# GeigerMuller_shield.net
KiCad netlist of a schematic drawn in EAGLE
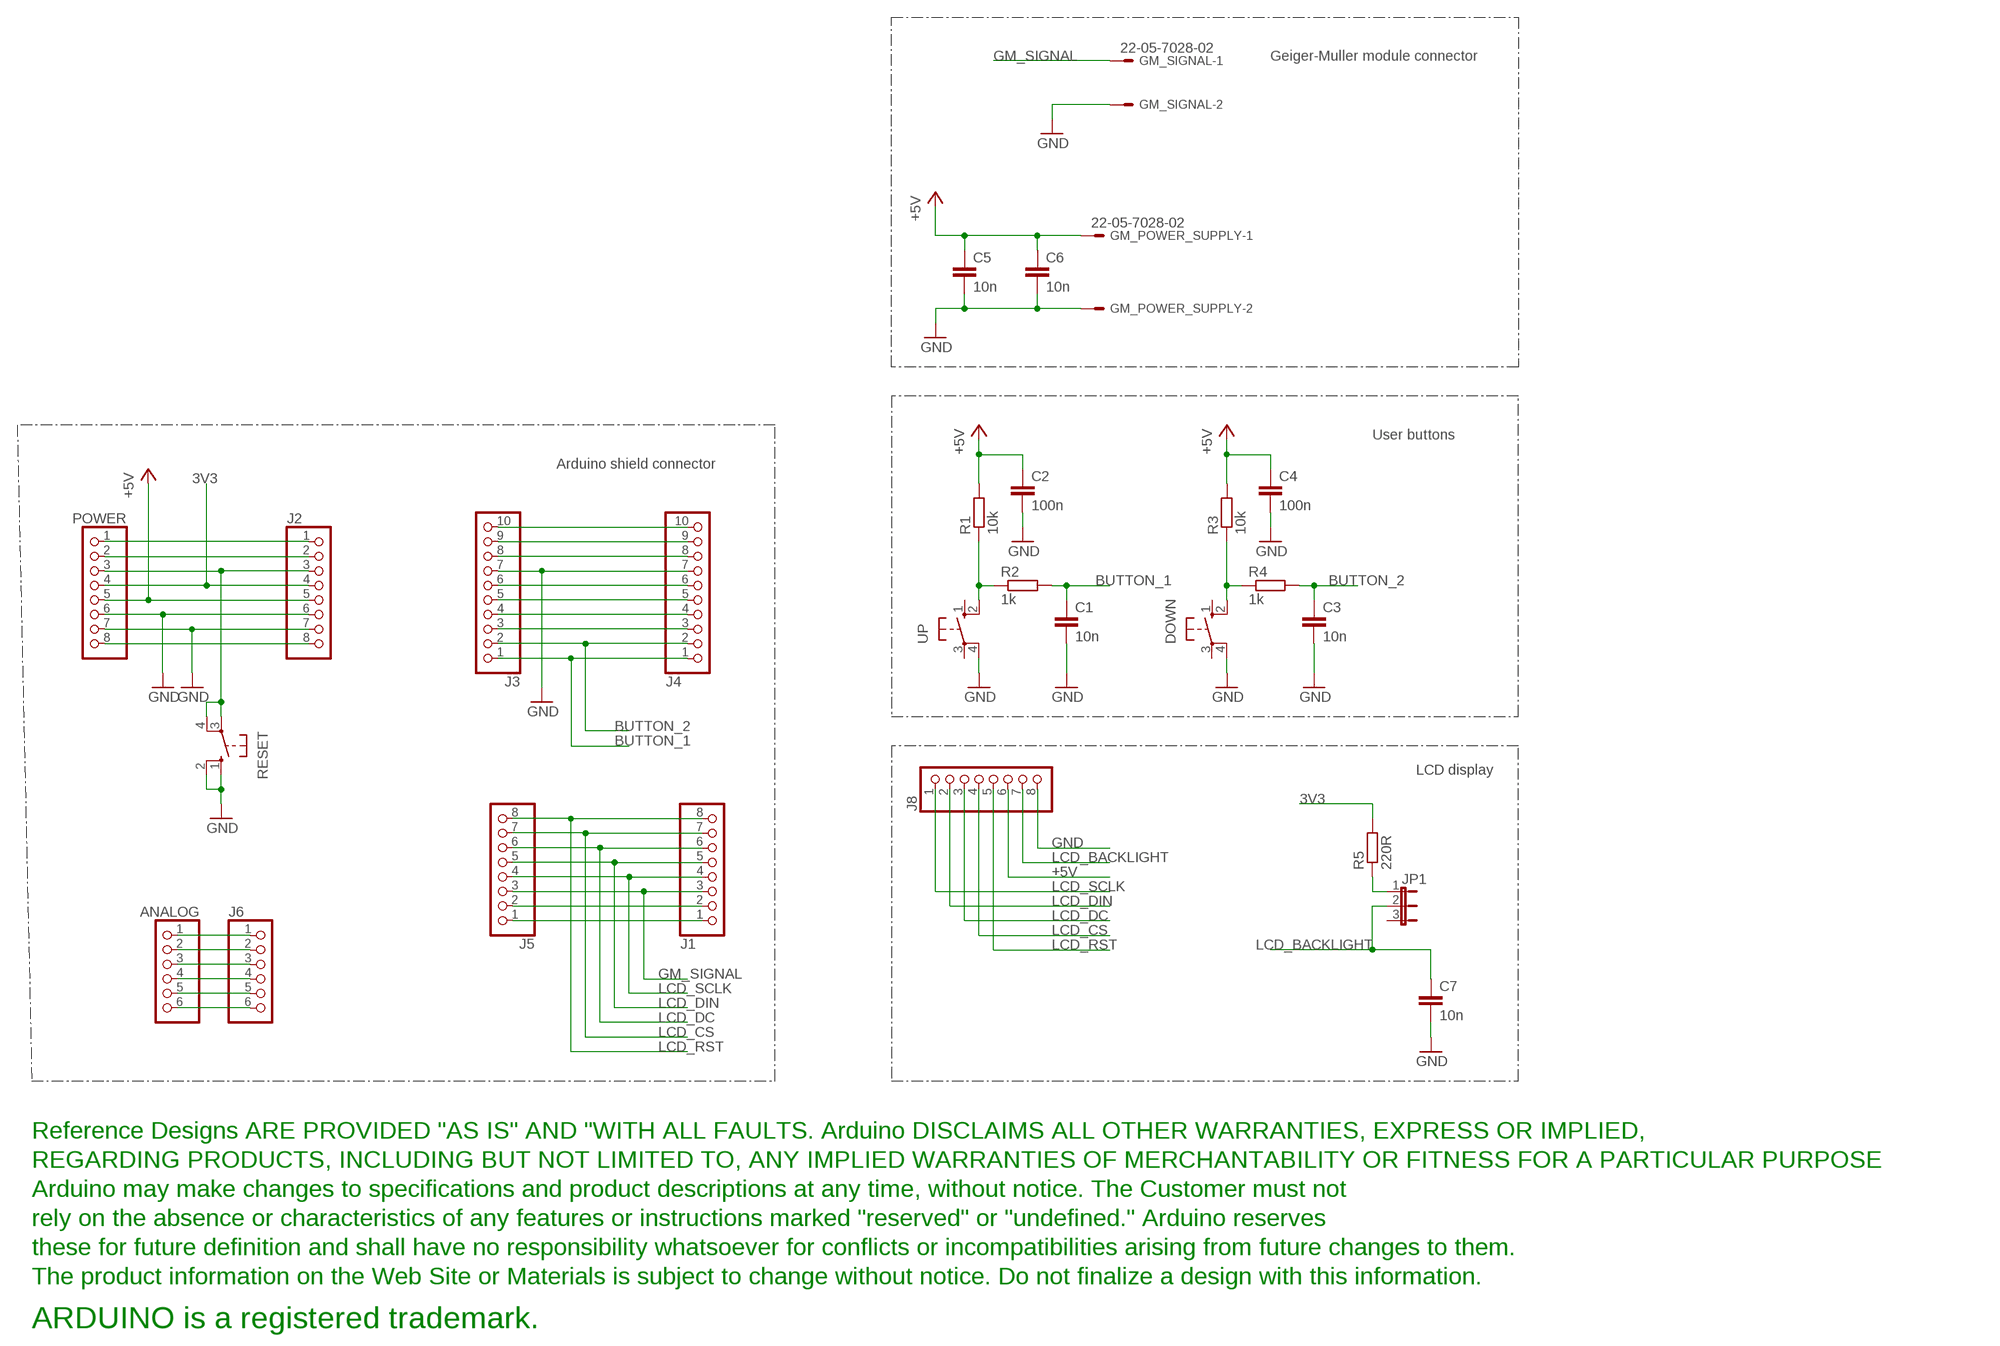
[diagram p0: schematic, sheet 1]

(export (version "E")
  (design (tool "Eeschema 10.0.6"))
  (components
    (comp (ref "ANALOG")
      (value "PINHD-1X6")
      (footprint "eagle-import:1X06")
      (libsource (lib "eagle-import") (part "PINHD-1X6"))
    )
    (comp (ref "C1")
      (value "10n")
      (footprint "eagle-import:C0805K")
      (libsource (lib "eagle-import") (part "C-EUC0805K"))
    )
    (comp (ref "C2")
      (value "100n")
      (footprint "eagle-import:C0805K")
      (libsource (lib "eagle-import") (part "C-EUC0805K"))
    )
    (comp (ref "C3")
      (value "10n")
      (footprint "eagle-import:C0805K")
      (libsource (lib "eagle-import") (part "C-EUC0805K"))
    )
    (comp (ref "C4")
      (value "100n")
      (footprint "eagle-import:C0805K")
      (libsource (lib "eagle-import") (part "C-EUC0805K"))
    )
    (comp (ref "C5")
      (value "10n")
      (footprint "eagle-import:C0805K")
      (libsource (lib "eagle-import") (part "C-EUC0805K"))
    )
    (comp (ref "C6")
      (value "10n")
      (footprint "eagle-import:C0805K")
      (libsource (lib "eagle-import") (part "C-EUC0805K"))
    )
    (comp (ref "C7")
      (value "10n")
      (footprint "eagle-import:C0805K")
      (libsource (lib "eagle-import") (part "C-EUC0805K"))
    )
    (comp (ref "DOWN")
      (value "10-XX")
      (footprint "eagle-import:B3F-10XX")
      (fields (field (name "MPN") "B3F-1000"))
      (libsource (lib "eagle-import") (part "10-XX"))
    )
    (comp (ref "GM_POWER_SUPPLY")
      (value "22-05-7028-02")
      (footprint "eagle-import:7395-02")
      (libsource (lib "eagle-import") (part "22-?-0205-7028"))
    )
    (comp (ref "GM_SIGNAL")
      (value "22-05-7028-02")
      (footprint "eagle-import:7395-02")
      (libsource (lib "eagle-import") (part "22-?-0205-7028"))
    )
    (comp (ref "J1")
      (value "PINHD-1X8TH")
      (footprint "eagle-import:1X08-TH")
      (libsource (lib "eagle-import") (part "PINHD-1X8TH"))
    )
    (comp (ref "J2")
      (value "PINHD-1X8TH")
      (footprint "eagle-import:1X08-TH")
      (libsource (lib "eagle-import") (part "PINHD-1X8TH"))
    )
    (comp (ref "J3")
      (value "PINHD-1X10TH")
      (footprint "eagle-import:1X10-TH")
      (libsource (lib "eagle-import") (part "PINHD-1X10TH"))
    )
    (comp (ref "J4")
      (value "PINHD-1X10TH")
      (footprint "eagle-import:1X10-TH")
      (libsource (lib "eagle-import") (part "PINHD-1X10TH"))
    )
    (comp (ref "J5")
      (value "PINHD-1X8TH")
      (footprint "eagle-import:1X08-TH")
      (libsource (lib "eagle-import") (part "PINHD-1X8TH"))
    )
    (comp (ref "J6")
      (value "PINHD-1X6")
      (footprint "eagle-import:1X06")
      (libsource (lib "eagle-import") (part "PINHD-1X6"))
    )
    (comp (ref "J8")
      (value "PINHD-1X8TH")
      (footprint "eagle-import:1X08-TH")
      (libsource (lib "eagle-import") (part "PINHD-1X8TH"))
    )
    (comp (ref "JP1")
      (value "JP2E")
      (footprint "eagle-import:JP2")
      (libsource (lib "eagle-import") (part "JP2E"))
    )
    (comp (ref "POWER")
      (value "PINHD-1X8TH")
      (footprint "eagle-import:1X08-TH")
      (libsource (lib "eagle-import") (part "PINHD-1X8TH"))
    )
    (comp (ref "R1")
      (value "10k")
      (footprint "eagle-import:R0805")
      (libsource (lib "eagle-import") (part "R-EU_R0805"))
    )
    (comp (ref "R2")
      (value "1k")
      (footprint "eagle-import:R0805")
      (libsource (lib "eagle-import") (part "R-EU_R0805"))
    )
    (comp (ref "R3")
      (value "10k")
      (footprint "eagle-import:R0805")
      (libsource (lib "eagle-import") (part "R-EU_R0805"))
    )
    (comp (ref "R4")
      (value "1k")
      (footprint "eagle-import:R0805")
      (libsource (lib "eagle-import") (part "R-EU_R0805"))
    )
    (comp (ref "R5")
      (value "220R")
      (footprint "eagle-import:0207_10")
      (libsource (lib "eagle-import") (part "R-EU_0207/10"))
    )
    (comp (ref "RESET")
      (value "10-XX")
      (footprint "eagle-import:B3F-10XX")
      (fields (field (name "MPN") "B3F-1000"))
      (libsource (lib "eagle-import") (part "10-XX"))
    )
    (comp (ref "U$1")
      (value "DISCLAIMER")
      (footprint "eagle-import:DISCLAIMER")
      (libsource (lib "eagle-import") (part "DISCLAIMER"))
    )
    (comp (ref "UP")
      (value "10-XX")
      (footprint "eagle-import:B3F-10XX")
      (fields (field (name "MPN") "B3F-1000"))
      (libsource (lib "eagle-import") (part "10-XX"))
    )
  )
  (nets
    (net (code "1") (name "+5V") (class "Default")
      (node (ref "C2") (pin "1") (pinfunction "1_1") (pintype "passive"))
      (node (ref "C4") (pin "1") (pinfunction "1_1") (pintype "passive"))
      (node (ref "C5") (pin "1") (pinfunction "1_1") (pintype "passive"))
      (node (ref "C6") (pin "1") (pinfunction "1_1") (pintype "passive"))
      (node (ref "GM_POWER_SUPPLY") (pin "1") (pinfunction "S_1") (pintype "passive"))
      (node (ref "J2") (pin "5") (pinfunction "5_5") (pintype "passive"))
      (node (ref "J8") (pin "6") (pinfunction "6_6") (pintype "passive"))
      (node (ref "POWER") (pin "5") (pinfunction "5_5") (pintype "passive"))
      (node (ref "R1") (pin "2") (pinfunction "2_2") (pintype "passive"))
      (node (ref "R3") (pin "2") (pinfunction "2_2") (pintype "passive"))
    )
    (net (code "2") (name "/3V3") (class "Default")
      (node (ref "J2") (pin "4") (pinfunction "4_4") (pintype "passive"))
      (node (ref "POWER") (pin "4") (pinfunction "4_4") (pintype "passive"))
      (node (ref "R5") (pin "2") (pinfunction "2_2") (pintype "passive"))
    )
    (net (code "3") (name "/BUTTON_1") (class "Default")
      (node (ref "C1") (pin "1") (pinfunction "1_1") (pintype "passive"))
      (node (ref "J3") (pin "1") (pinfunction "1_1") (pintype "passive"))
      (node (ref "J4") (pin "1") (pinfunction "1_1") (pintype "passive"))
      (node (ref "R2") (pin "2") (pinfunction "2_2") (pintype "passive"))
    )
    (net (code "4") (name "/BUTTON_2") (class "Default")
      (node (ref "C3") (pin "1") (pinfunction "1_1") (pintype "passive"))
      (node (ref "J3") (pin "2") (pinfunction "2_2") (pintype "passive"))
      (node (ref "J4") (pin "2") (pinfunction "2_2") (pintype "passive"))
      (node (ref "R4") (pin "2") (pinfunction "2_2") (pintype "passive"))
    )
    (net (code "5") (name "/GM_SIGNAL") (class "Default")
      (node (ref "GM_SIGNAL") (pin "1") (pinfunction "S_1") (pintype "passive"))
      (node (ref "J1") (pin "3") (pinfunction "3_3") (pintype "passive"))
      (node (ref "J5") (pin "3") (pinfunction "3_3") (pintype "passive"))
    )
    (net (code "6") (name "/LCD_BACKLIGHT") (class "Default")
      (node (ref "C7") (pin "1") (pinfunction "1_1") (pintype "passive"))
      (node (ref "J8") (pin "7") (pinfunction "7_7") (pintype "passive"))
      (node (ref "JP1") (pin "2") (pinfunction "2_2") (pintype "passive"))
    )
    (net (code "7") (name "/LCD_CS") (class "Default")
      (node (ref "J1") (pin "7") (pinfunction "7_7") (pintype "passive"))
      (node (ref "J5") (pin "7") (pinfunction "7_7") (pintype "passive"))
      (node (ref "J8") (pin "4") (pinfunction "4_4") (pintype "passive"))
    )
    (net (code "8") (name "/LCD_DC") (class "Default")
      (node (ref "J1") (pin "6") (pinfunction "6_6") (pintype "passive"))
      (node (ref "J5") (pin "6") (pinfunction "6_6") (pintype "passive"))
      (node (ref "J8") (pin "3") (pinfunction "3_3") (pintype "passive"))
    )
    (net (code "9") (name "/LCD_DIN") (class "Default")
      (node (ref "J1") (pin "5") (pinfunction "5_5") (pintype "passive"))
      (node (ref "J5") (pin "5") (pinfunction "5_5") (pintype "passive"))
      (node (ref "J8") (pin "2") (pinfunction "2_2") (pintype "passive"))
    )
    (net (code "10") (name "/LCD_RST") (class "Default")
      (node (ref "J1") (pin "8") (pinfunction "8_8") (pintype "passive"))
      (node (ref "J5") (pin "8") (pinfunction "8_8") (pintype "passive"))
      (node (ref "J8") (pin "5") (pinfunction "5_5") (pintype "passive"))
    )
    (net (code "11") (name "/LCD_SCLK") (class "Default")
      (node (ref "J1") (pin "4") (pinfunction "4_4") (pintype "passive"))
      (node (ref "J5") (pin "4") (pinfunction "4_4") (pintype "passive"))
      (node (ref "J8") (pin "1") (pinfunction "1_1") (pintype "passive"))
    )
    (net (code "12") (name "GND") (class "Default")
      (node (ref "C1") (pin "2") (pinfunction "2_2") (pintype "passive"))
      (node (ref "C2") (pin "2") (pinfunction "2_2") (pintype "passive"))
      (node (ref "C3") (pin "2") (pinfunction "2_2") (pintype "passive"))
      (node (ref "C4") (pin "2") (pinfunction "2_2") (pintype "passive"))
      (node (ref "C5") (pin "2") (pinfunction "2_2") (pintype "passive"))
      (node (ref "C6") (pin "2") (pinfunction "2_2") (pintype "passive"))
      (node (ref "C7") (pin "2") (pinfunction "2_2") (pintype "passive"))
      (node (ref "DOWN") (pin "4") (pinfunction "P1_4") (pintype "passive"))
      (node (ref "GM_POWER_SUPPLY") (pin "2") (pinfunction "S_2") (pintype "passive"))
      (node (ref "GM_SIGNAL") (pin "2") (pinfunction "S_2") (pintype "passive"))
      (node (ref "J2") (pin "6") (pinfunction "6_6") (pintype "passive"))
      (node (ref "J2") (pin "7") (pinfunction "7_7") (pintype "passive"))
      (node (ref "J3") (pin "7") (pinfunction "7_7") (pintype "passive"))
      (node (ref "J4") (pin "7") (pinfunction "7_7") (pintype "passive"))
      (node (ref "J8") (pin "8") (pinfunction "8_8") (pintype "passive"))
      (node (ref "POWER") (pin "6") (pinfunction "6_6") (pintype "passive"))
      (node (ref "POWER") (pin "7") (pinfunction "7_7") (pintype "passive"))
      (node (ref "RESET") (pin "1") (pinfunction "S_1") (pintype "passive"))
      (node (ref "RESET") (pin "2") (pinfunction "S1_2") (pintype "passive"))
      (node (ref "UP") (pin "4") (pinfunction "P1_4") (pintype "passive"))
    )
    (net (code "13") (name "Net-(ANALOG-Pad1)") (class "Default")
      (node (ref "ANALOG") (pin "1") (pinfunction "1_1") (pintype "passive"))
      (node (ref "J6") (pin "1") (pinfunction "1_1") (pintype "passive"))
    )
    (net (code "14") (name "Net-(ANALOG-Pad2)") (class "Default")
      (node (ref "ANALOG") (pin "2") (pinfunction "2_2") (pintype "passive"))
      (node (ref "J6") (pin "2") (pinfunction "2_2") (pintype "passive"))
    )
    (net (code "15") (name "Net-(ANALOG-Pad3)") (class "Default")
      (node (ref "ANALOG") (pin "3") (pinfunction "3_3") (pintype "passive"))
      (node (ref "J6") (pin "3") (pinfunction "3_3") (pintype "passive"))
    )
    (net (code "16") (name "Net-(ANALOG-Pad4)") (class "Default")
      (node (ref "ANALOG") (pin "4") (pinfunction "4_4") (pintype "passive"))
      (node (ref "J6") (pin "4") (pinfunction "4_4") (pintype "passive"))
    )
    (net (code "17") (name "Net-(ANALOG-Pad5)") (class "Default")
      (node (ref "ANALOG") (pin "5") (pinfunction "5_5") (pintype "passive"))
      (node (ref "J6") (pin "5") (pinfunction "5_5") (pintype "passive"))
    )
    (net (code "18") (name "Net-(ANALOG-Pad6)") (class "Default")
      (node (ref "ANALOG") (pin "6") (pinfunction "6_6") (pintype "passive"))
      (node (ref "J6") (pin "6") (pinfunction "6_6") (pintype "passive"))
    )
    (net (code "19") (name "Net-(DOWN-S1)") (class "Default")
      (node (ref "DOWN") (pin "2") (pinfunction "S1_2") (pintype "passive"))
      (node (ref "R3") (pin "1") (pinfunction "1_1") (pintype "passive"))
      (node (ref "R4") (pin "1") (pinfunction "1_1") (pintype "passive"))
    )
    (net (code "20") (name "Net-(J1-Pad1)") (class "Default")
      (node (ref "J1") (pin "1") (pinfunction "1_1") (pintype "passive"))
      (node (ref "J5") (pin "1") (pinfunction "1_1") (pintype "passive"))
    )
    (net (code "21") (name "Net-(J1-Pad2)") (class "Default")
      (node (ref "J1") (pin "2") (pinfunction "2_2") (pintype "passive"))
      (node (ref "J5") (pin "2") (pinfunction "2_2") (pintype "passive"))
    )
    (net (code "22") (name "Net-(J2-Pad1)") (class "Default")
      (node (ref "J2") (pin "1") (pinfunction "1_1") (pintype "passive"))
      (node (ref "POWER") (pin "1") (pinfunction "1_1") (pintype "passive"))
    )
    (net (code "23") (name "Net-(J2-Pad2)") (class "Default")
      (node (ref "J2") (pin "2") (pinfunction "2_2") (pintype "passive"))
      (node (ref "POWER") (pin "2") (pinfunction "2_2") (pintype "passive"))
    )
    (net (code "24") (name "Net-(J2-Pad8)") (class "Default")
      (node (ref "J2") (pin "8") (pinfunction "8_8") (pintype "passive"))
      (node (ref "POWER") (pin "8") (pinfunction "8_8") (pintype "passive"))
    )
    (net (code "25") (name "Net-(J3-Pad3)") (class "Default")
      (node (ref "J3") (pin "3") (pinfunction "3_3") (pintype "passive"))
      (node (ref "J4") (pin "3") (pinfunction "3_3") (pintype "passive"))
    )
    (net (code "26") (name "Net-(J3-Pad4)") (class "Default")
      (node (ref "J3") (pin "4") (pinfunction "4_4") (pintype "passive"))
      (node (ref "J4") (pin "4") (pinfunction "4_4") (pintype "passive"))
    )
    (net (code "27") (name "Net-(J3-Pad5)") (class "Default")
      (node (ref "J3") (pin "5") (pinfunction "5_5") (pintype "passive"))
      (node (ref "J4") (pin "5") (pinfunction "5_5") (pintype "passive"))
    )
    (net (code "28") (name "Net-(J3-Pad6)") (class "Default")
      (node (ref "J3") (pin "6") (pinfunction "6_6") (pintype "passive"))
      (node (ref "J4") (pin "6") (pinfunction "6_6") (pintype "passive"))
    )
    (net (code "29") (name "Net-(J3-Pad8)") (class "Default")
      (node (ref "J3") (pin "8") (pinfunction "8_8") (pintype "passive"))
      (node (ref "J4") (pin "8") (pinfunction "8_8") (pintype "passive"))
    )
    (net (code "30") (name "Net-(J3-Pad9)") (class "Default")
      (node (ref "J3") (pin "9") (pinfunction "9_9") (pintype "passive"))
      (node (ref "J4") (pin "9") (pinfunction "9_9") (pintype "passive"))
    )
    (net (code "31") (name "Net-(J3-Pad10)") (class "Default")
      (node (ref "J3") (pin "10") (pinfunction "10_10") (pintype "passive"))
      (node (ref "J4") (pin "10") (pinfunction "10_10") (pintype "passive"))
    )
    (net (code "32") (name "Net-(JP1-Pad1)") (class "Default")
      (node (ref "JP1") (pin "1") (pinfunction "1_1") (pintype "passive"))
      (node (ref "R5") (pin "1") (pinfunction "1_1") (pintype "passive"))
    )
    (net (code "33") (name "Net-(RESET-P)") (class "Default")
      (node (ref "J2") (pin "3") (pinfunction "3_3") (pintype "passive"))
      (node (ref "POWER") (pin "3") (pinfunction "3_3") (pintype "passive"))
      (node (ref "RESET") (pin "3") (pinfunction "P_3") (pintype "passive"))
      (node (ref "RESET") (pin "4") (pinfunction "P1_4") (pintype "passive"))
    )
    (net (code "34") (name "Net-(UP-S1)") (class "Default")
      (node (ref "R1") (pin "1") (pinfunction "1_1") (pintype "passive"))
      (node (ref "R2") (pin "1") (pinfunction "1_1") (pintype "passive"))
      (node (ref "UP") (pin "2") (pinfunction "S1_2") (pintype "passive"))
    )
    (net (code "35") (name "unconnected-(DOWN-P-Pad3)") (class "Default")
      (node (ref "DOWN") (pin "3") (pinfunction "P_3") (pintype "passive"))
    )
    (net (code "36") (name "unconnected-(DOWN-S-Pad1)") (class "Default")
      (node (ref "DOWN") (pin "1") (pinfunction "S_1") (pintype "passive"))
    )
    (net (code "37") (name "unconnected-(JP1-Pad3)") (class "Default")
      (node (ref "JP1") (pin "3") (pinfunction "3_3") (pintype "passive"))
    )
    (net (code "38") (name "unconnected-(UP-P-Pad3)") (class "Default")
      (node (ref "UP") (pin "3") (pinfunction "P_3") (pintype "passive"))
    )
    (net (code "39") (name "unconnected-(UP-S-Pad1)") (class "Default")
      (node (ref "UP") (pin "1") (pinfunction "S_1") (pintype "passive"))
    )
  )
)
